# Sensor_Module_0x07_Heat_Flux.net
KiCad netlist of a schematic drawn in EAGLE
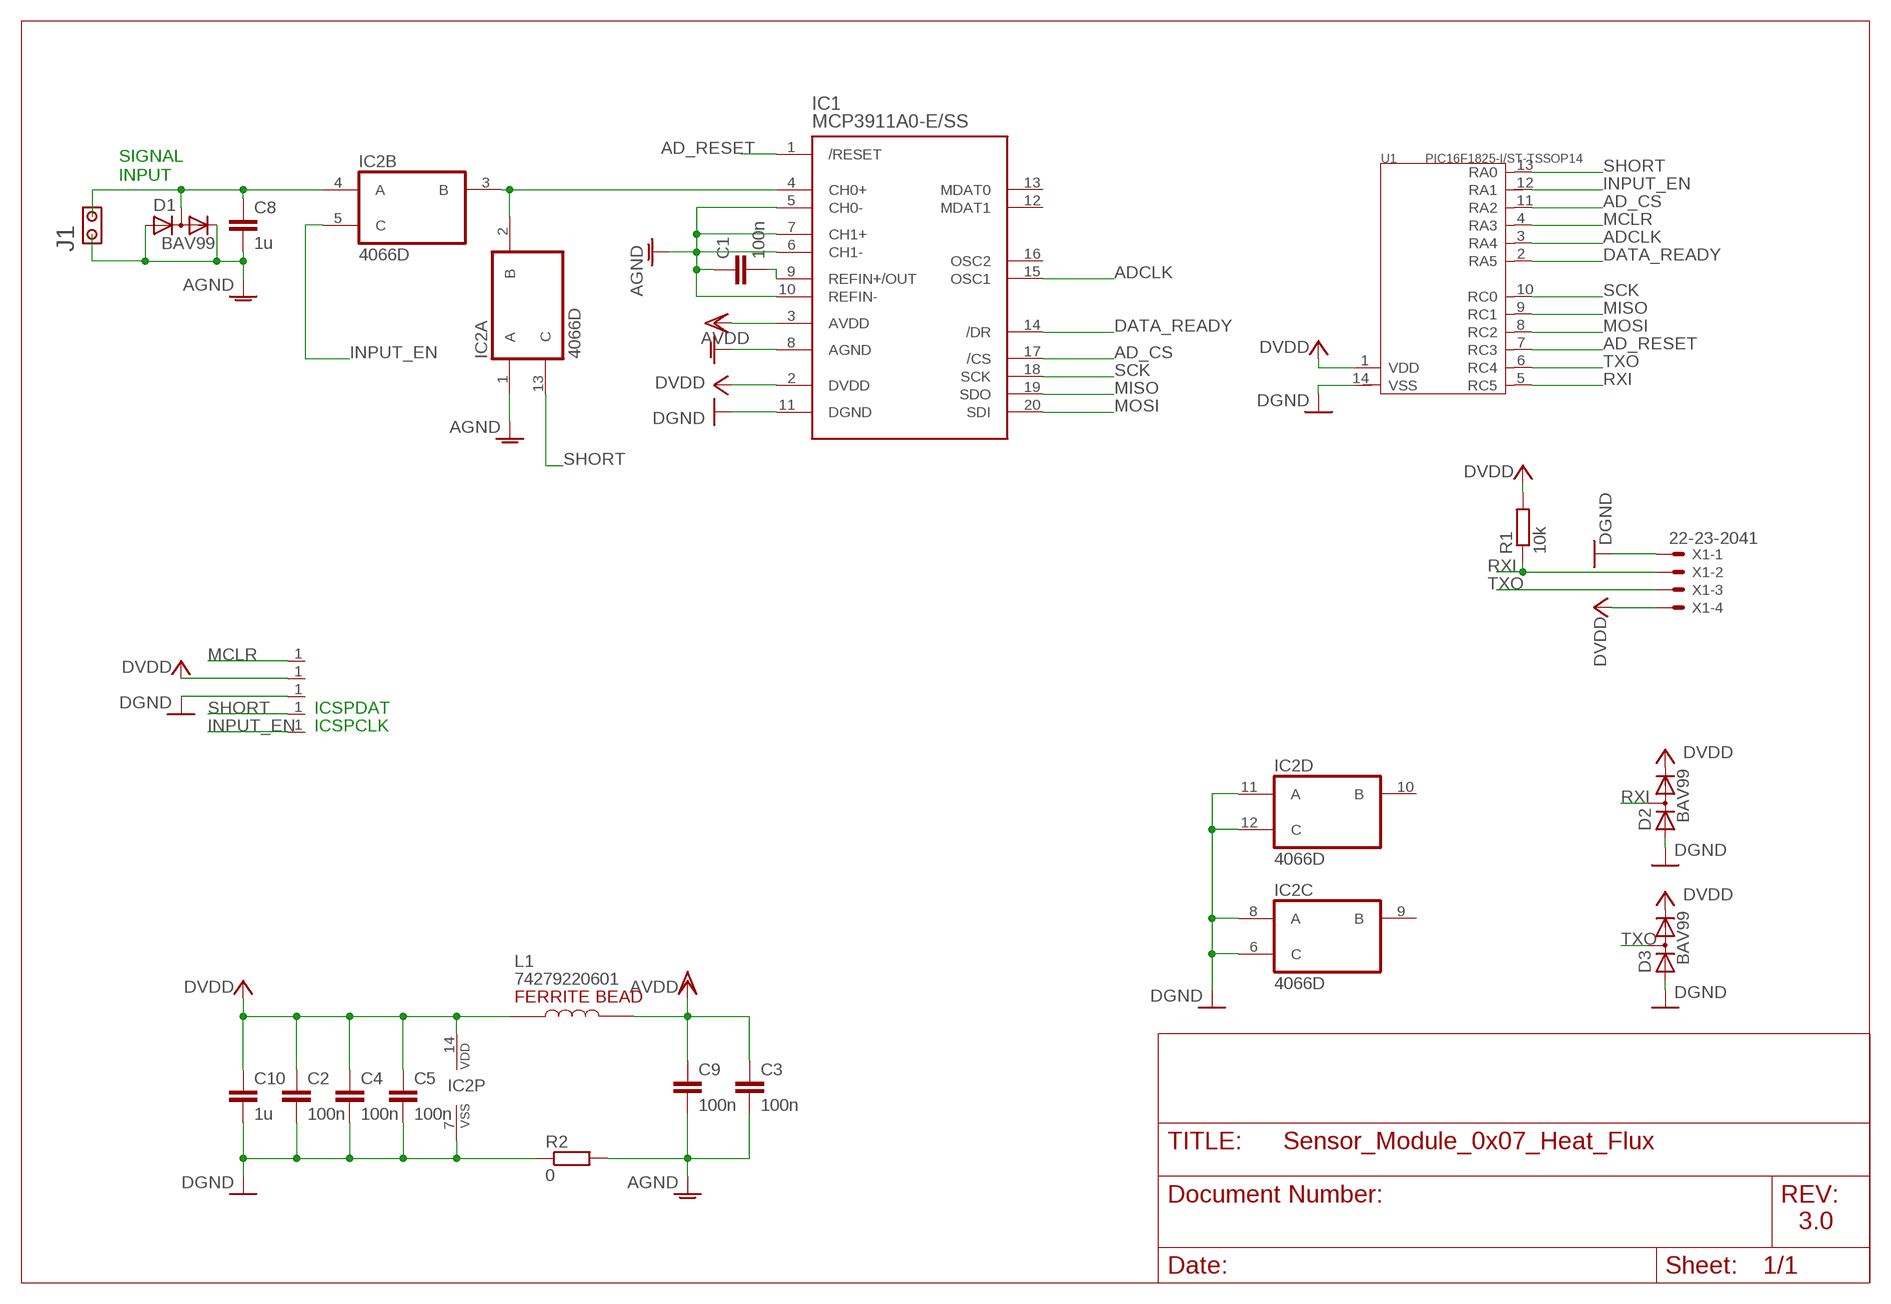
[diagram p0: schematic, sheet 1]

(export (version "E")
  (design (tool "Eeschema 10.0.6"))
  (components
    (comp (ref "C1")
      (value "100n")
      (footprint "eagle-import:C0805")
      (libsource (lib "eagle-import") (part "C-EUC0805"))
    )
    (comp (ref "C2")
      (value "100n")
      (footprint "eagle-import:C0805")
      (libsource (lib "eagle-import") (part "C-EUC0805"))
    )
    (comp (ref "C3")
      (value "100n")
      (footprint "eagle-import:C0805")
      (libsource (lib "eagle-import") (part "C-EUC0805"))
    )
    (comp (ref "C4")
      (value "100n")
      (footprint "eagle-import:C0805")
      (libsource (lib "eagle-import") (part "C-EUC0805"))
    )
    (comp (ref "C5")
      (value "100n")
      (footprint "eagle-import:C0805")
      (libsource (lib "eagle-import") (part "C-EUC0805"))
    )
    (comp (ref "C8")
      (value "1u")
      (footprint "eagle-import:C0805")
      (libsource (lib "eagle-import") (part "C-EUC0805"))
    )
    (comp (ref "C9")
      (value "100n")
      (footprint "eagle-import:C0805")
      (libsource (lib "eagle-import") (part "C-EUC0805"))
    )
    (comp (ref "C10")
      (value "1u")
      (footprint "eagle-import:C0805")
      (libsource (lib "eagle-import") (part "C-EUC0805"))
    )
    (comp (ref "D1")
      (value "BAV99")
      (footprint "eagle-import:SOT23")
      (libsource (lib "eagle-import") (part "BAV99"))
    )
    (comp (ref "D2")
      (value "BAV99")
      (footprint "eagle-import:SOT23")
      (libsource (lib "eagle-import") (part "BAV99"))
    )
    (comp (ref "D3")
      (value "BAV99")
      (footprint "eagle-import:SOT23")
      (libsource (lib "eagle-import") (part "BAV99"))
    )
    (comp (ref "IC1")
      (value "MCP3911A0-E/SS")
      (footprint "eagle-import:SSOP20")
      (fields (field (name "SPICEPREFIX") "X"))
      (libsource (lib "eagle-import") (part "MCP3911A0-E/SS"))
    )
    (comp (ref "IC2")
      (value "4066D")
      (footprint "eagle-import:SO14")
      (libsource (lib "eagle-import") (part "4066D"))
    )
    (comp (ref "J1")
      (value "CON2X1")
      (footprint "eagle-import:CON2X1")
      (libsource (lib "eagle-import") (part "CON2X1"))
    )
    (comp (ref "L1")
      (value "74279220601")
      (footprint "eagle-import:0805")
      (libsource (lib "eagle-import") (part "74279220601"))
    )
    (comp (ref "PIN1")
      (value "CON1X1")
      (footprint "eagle-import:CON1X1")
      (libsource (lib "eagle-import") (part "CON1X1"))
    )
    (comp (ref "PIN2")
      (value "CON1X1")
      (footprint "eagle-import:CON1X1")
      (libsource (lib "eagle-import") (part "CON1X1"))
    )
    (comp (ref "PIN3")
      (value "CON1X1")
      (footprint "eagle-import:CON1X1")
      (libsource (lib "eagle-import") (part "CON1X1"))
    )
    (comp (ref "PIN4")
      (value "CON1X1")
      (footprint "eagle-import:CON1X1")
      (libsource (lib "eagle-import") (part "CON1X1"))
    )
    (comp (ref "PIN5")
      (value "CON1X1")
      (footprint "eagle-import:CON1X1")
      (libsource (lib "eagle-import") (part "CON1X1"))
    )
    (comp (ref "R1")
      (value "10k")
      (footprint "eagle-import:M0805")
      (libsource (lib "eagle-import") (part "R-EU_M0805"))
    )
    (comp (ref "R2")
      (value "0")
      (footprint "eagle-import:M0805")
      (libsource (lib "eagle-import") (part "R-EU_M0805"))
    )
    (comp (ref "U1")
      (value "PIC16F1825-I/ST-TSSOP14")
      (footprint "eagle-import:TSSOP14-0.65-5X4.4MM")
      (fields (field (name "MPN") "PIC16F1825-I/ST"))
      (libsource (lib "eagle-import") (part "MCU-PIC16F1825-I/ST(TSSOP14)"))
    )
    (comp (ref "X1")
      (value "22-23-2041")
      (footprint "eagle-import:22-23-2041")
      (fields (field (name "MF") "MOLEX"))
      (libsource (lib "eagle-import") (part "22-23-2041"))
    )
  )
  (nets
    (net (code "1") (name "/ADCLK") (class "Default")
      (node (ref "IC1") (pin "15") (pinfunction "OSC1_15") (pintype "bidirectional"))
      (node (ref "U1") (pin "3") (pinfunction "RA4_3") (pintype "bidirectional"))
    )
    (net (code "2") (name "/AD_CS") (class "Default")
      (node (ref "IC1") (pin "17") (pinfunction "/CS_17") (pintype "bidirectional"))
      (node (ref "U1") (pin "11") (pinfunction "RA2_11") (pintype "bidirectional"))
    )
    (net (code "3") (name "/AD_RESET") (class "Default")
      (node (ref "IC1") (pin "1") (pinfunction "/RESET_1") (pintype "bidirectional"))
      (node (ref "U1") (pin "7") (pinfunction "RC3_7") (pintype "bidirectional"))
    )
    (net (code "4") (name "/DATA_READY") (class "Default")
      (node (ref "IC1") (pin "14") (pinfunction "/DR_14") (pintype "bidirectional"))
      (node (ref "U1") (pin "2") (pinfunction "RA5_2") (pintype "bidirectional"))
    )
    (net (code "5") (name "/INPUT_EN") (class "Default")
      (node (ref "IC2") (pin "5") (pinfunction "C_5") (pintype "input"))
      (node (ref "PIN5") (pin "1") (pinfunction "1_1") (pintype "passive"))
      (node (ref "U1") (pin "12") (pinfunction "RA1_12") (pintype "bidirectional"))
    )
    (net (code "6") (name "/MCLR") (class "Default")
      (node (ref "PIN1") (pin "1") (pinfunction "1_1") (pintype "passive"))
      (node (ref "U1") (pin "4") (pinfunction "RA3_4") (pintype "bidirectional"))
    )
    (net (code "7") (name "/MISO") (class "Default")
      (node (ref "IC1") (pin "19") (pinfunction "SDO_19") (pintype "bidirectional"))
      (node (ref "U1") (pin "9") (pinfunction "RC1_9") (pintype "bidirectional"))
    )
    (net (code "8") (name "/MOSI") (class "Default")
      (node (ref "IC1") (pin "20") (pinfunction "SDI_20") (pintype "bidirectional"))
      (node (ref "U1") (pin "8") (pinfunction "RC2_8") (pintype "bidirectional"))
    )
    (net (code "9") (name "/RXI") (class "Default")
      (node (ref "D2") (pin "3") (pinfunction "AC_3") (pintype "passive"))
      (node (ref "R1") (pin "1") (pinfunction "1_1") (pintype "passive"))
      (node (ref "U1") (pin "5") (pinfunction "RC5_5") (pintype "bidirectional"))
      (node (ref "X1") (pin "2") (pinfunction "S_2") (pintype "passive"))
    )
    (net (code "10") (name "/SCK") (class "Default")
      (node (ref "IC1") (pin "18") (pinfunction "SCK_18") (pintype "bidirectional"))
      (node (ref "U1") (pin "10") (pinfunction "RC0_10") (pintype "bidirectional"))
    )
    (net (code "11") (name "/SHORT") (class "Default")
      (node (ref "IC2") (pin "13") (pinfunction "C_13") (pintype "input"))
      (node (ref "PIN4") (pin "1") (pinfunction "1_1") (pintype "passive"))
      (node (ref "U1") (pin "13") (pinfunction "RA0_13") (pintype "bidirectional"))
    )
    (net (code "12") (name "/TXO") (class "Default")
      (node (ref "D3") (pin "3") (pinfunction "AC_3") (pintype "passive"))
      (node (ref "U1") (pin "6") (pinfunction "RC4_6") (pintype "bidirectional"))
      (node (ref "X1") (pin "3") (pinfunction "S_3") (pintype "passive"))
    )
    (net (code "13") (name "AGND") (class "Default")
      (node (ref "C1") (pin "1") (pinfunction "1_1") (pintype "passive"))
      (node (ref "C3") (pin "2") (pinfunction "2_2") (pintype "passive"))
      (node (ref "C8") (pin "2") (pinfunction "2_2") (pintype "passive"))
      (node (ref "C9") (pin "2") (pinfunction "2_2") (pintype "passive"))
      (node (ref "D1") (pin "1") (pinfunction "A_1") (pintype "passive"))
      (node (ref "D1") (pin "2") (pinfunction "C_2") (pintype "passive"))
      (node (ref "IC1") (pin "10") (pinfunction "REFIN-_10") (pintype "bidirectional"))
      (node (ref "IC1") (pin "5") (pinfunction "CH0-_5") (pintype "bidirectional"))
      (node (ref "IC1") (pin "6") (pinfunction "CH1-_6") (pintype "bidirectional"))
      (node (ref "IC1") (pin "7") (pinfunction "CH1+_7") (pintype "bidirectional"))
      (node (ref "IC1") (pin "8") (pinfunction "AGND_8") (pintype "bidirectional"))
      (node (ref "IC2") (pin "1") (pinfunction "A_1") (pintype "tri_state"))
      (node (ref "J1") (pin "1") (pinfunction "1_1") (pintype "input"))
      (node (ref "R2") (pin "2") (pinfunction "2_2") (pintype "passive"))
    )
    (net (code "14") (name "AVDD") (class "Default")
      (node (ref "C3") (pin "1") (pinfunction "1_1") (pintype "passive"))
      (node (ref "C9") (pin "1") (pinfunction "1_1") (pintype "passive"))
      (node (ref "IC1") (pin "3") (pinfunction "AVDD_3") (pintype "bidirectional"))
      (node (ref "L1") (pin "2") (pinfunction "P$2_2") (pintype "bidirectional"))
    )
    (net (code "15") (name "DGND") (class "Default")
      (node (ref "C10") (pin "2") (pinfunction "2_2") (pintype "passive"))
      (node (ref "C2") (pin "2") (pinfunction "2_2") (pintype "passive"))
      (node (ref "C4") (pin "2") (pinfunction "2_2") (pintype "passive"))
      (node (ref "C5") (pin "2") (pinfunction "2_2") (pintype "passive"))
      (node (ref "D2") (pin "1") (pinfunction "A_1") (pintype "passive"))
      (node (ref "D3") (pin "1") (pinfunction "A_1") (pintype "passive"))
      (node (ref "IC1") (pin "11") (pinfunction "DGND_11") (pintype "bidirectional"))
      (node (ref "IC2") (pin "11") (pinfunction "A_11") (pintype "tri_state"))
      (node (ref "IC2") (pin "12") (pinfunction "C_12") (pintype "input"))
      (node (ref "IC2") (pin "6") (pinfunction "C_6") (pintype "input"))
      (node (ref "IC2") (pin "7") (pinfunction "VSS_7") (pintype "power_in"))
      (node (ref "IC2") (pin "8") (pinfunction "A_8") (pintype "tri_state"))
      (node (ref "PIN3") (pin "1") (pinfunction "1_1") (pintype "passive"))
      (node (ref "R2") (pin "1") (pinfunction "1_1") (pintype "passive"))
      (node (ref "U1") (pin "14") (pinfunction "VSS_14") (pintype "bidirectional"))
      (node (ref "X1") (pin "1") (pinfunction "S_1") (pintype "passive"))
    )
    (net (code "16") (name "DVDD") (class "Default")
      (node (ref "C10") (pin "1") (pinfunction "1_1") (pintype "passive"))
      (node (ref "C2") (pin "1") (pinfunction "1_1") (pintype "passive"))
      (node (ref "C4") (pin "1") (pinfunction "1_1") (pintype "passive"))
      (node (ref "C5") (pin "1") (pinfunction "1_1") (pintype "passive"))
      (node (ref "D2") (pin "2") (pinfunction "C_2") (pintype "passive"))
      (node (ref "D3") (pin "2") (pinfunction "C_2") (pintype "passive"))
      (node (ref "IC1") (pin "2") (pinfunction "DVDD_2") (pintype "bidirectional"))
      (node (ref "IC2") (pin "14") (pinfunction "VDD_14") (pintype "power_in"))
      (node (ref "L1") (pin "1") (pinfunction "P$1_1") (pintype "bidirectional"))
      (node (ref "PIN2") (pin "1") (pinfunction "1_1") (pintype "passive"))
      (node (ref "R1") (pin "2") (pinfunction "2_2") (pintype "passive"))
      (node (ref "U1") (pin "1") (pinfunction "VDD_1") (pintype "bidirectional"))
      (node (ref "X1") (pin "4") (pinfunction "S_4") (pintype "passive"))
    )
    (net (code "17") (name "Net-(D1-AC)") (class "Default")
      (node (ref "C8") (pin "1") (pinfunction "1_1") (pintype "passive"))
      (node (ref "D1") (pin "3") (pinfunction "AC_3") (pintype "passive"))
      (node (ref "IC2") (pin "4") (pinfunction "A_4") (pintype "tri_state"))
      (node (ref "J1") (pin "2") (pinfunction "2_2") (pintype "input"))
    )
    (net (code "18") (name "Net-(IC1-CH0+)") (class "Default")
      (node (ref "IC1") (pin "4") (pinfunction "CH0+_4") (pintype "bidirectional"))
      (node (ref "IC2") (pin "2") (pinfunction "B_2") (pintype "tri_state"))
      (node (ref "IC2") (pin "3") (pinfunction "B_3") (pintype "tri_state"))
    )
    (net (code "19") (name "Net-(IC1-REFIN+{slash}OUT)") (class "Default")
      (node (ref "C1") (pin "2") (pinfunction "2_2") (pintype "passive"))
      (node (ref "IC1") (pin "9") (pinfunction "REFIN+/OUT_9") (pintype "bidirectional"))
    )
    (net (code "20") (name "unconnected-(IC1-MDAT0-Pad13)") (class "Default")
      (node (ref "IC1") (pin "13") (pinfunction "MDAT0_13") (pintype "bidirectional"))
    )
    (net (code "21") (name "unconnected-(IC1-MDAT1-Pad12)") (class "Default")
      (node (ref "IC1") (pin "12") (pinfunction "MDAT1_12") (pintype "bidirectional"))
    )
    (net (code "22") (name "unconnected-(IC1-OSC2-Pad16)") (class "Default")
      (node (ref "IC1") (pin "16") (pinfunction "OSC2_16") (pintype "bidirectional"))
    )
    (net (code "23") (name "unconnected-(IC2C-B-Pad9)") (class "Default")
      (node (ref "IC2") (pin "9") (pinfunction "B_9") (pintype "tri_state"))
    )
    (net (code "24") (name "unconnected-(IC2D-B-Pad10)") (class "Default")
      (node (ref "IC2") (pin "10") (pinfunction "B_10") (pintype "tri_state"))
    )
  )
)
